# MCPS_Supply_030523.net
KiCad netlist of a schematic drawn in Altium Designer
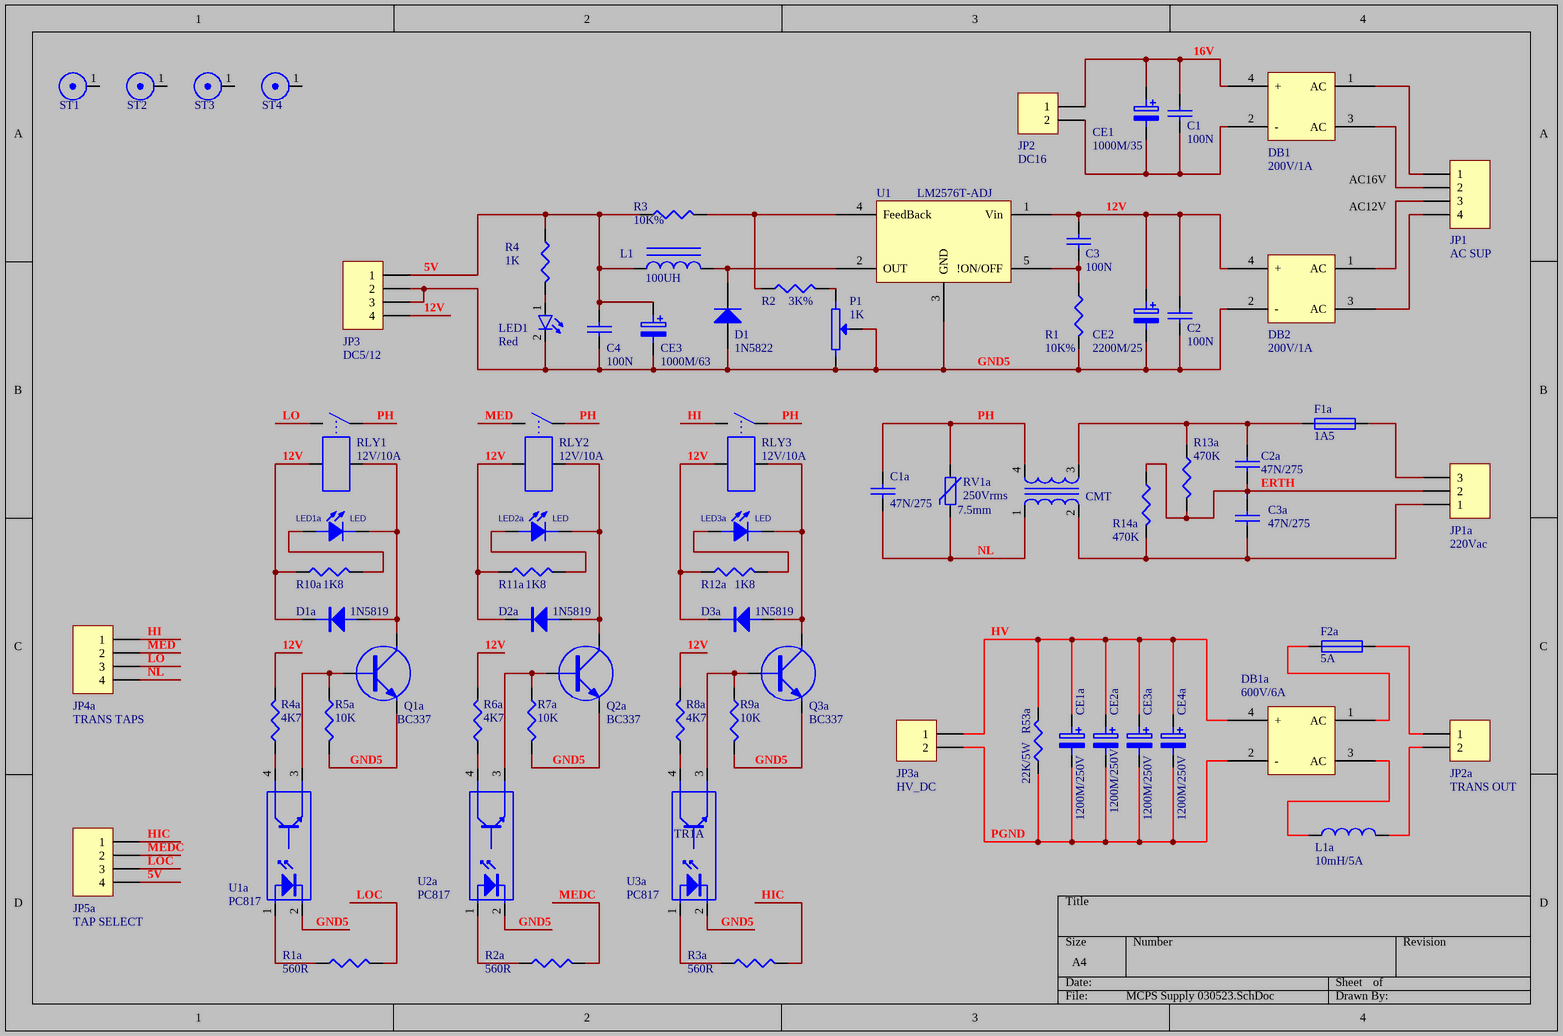
[diagram p0: MCPS Supply 030523.SchDoc]

(export (version "E")
  (design (tool "Eeschema 10.0.6"))
  (components
    (comp (ref "C1") (value "100N") (footprint "c1.8p") (libsource (lib "*") (part "C")))
    (comp (ref "C1a") (value "47N/275") (footprint "47N275") (libsource (lib "*") (part "C")))
    (comp (ref "C2") (value "100N") (footprint "c1.8p") (libsource (lib "*") (part "C")))
    (comp (ref "C2a") (value "47N/275") (footprint "47N275") (libsource (lib "*") (part "C")))
    (comp (ref "C3") (value "100N") (footprint "C3P") (libsource (lib "*") (part "C")))
    (comp (ref "C3a") (value "47N/275") (footprint "47N275") (libsource (lib "*") (part "C")))
    (comp (ref "C4") (value "100N") (footprint "c1.8p") (libsource (lib "*") (part "C")))
    (comp (ref "CE1") (value "1000M/35") (footprint "CAP3P") (libsource (lib "*") (part "E")))
    (comp (ref "CE1a") (value "1200M/250V") (footprint "CAP5P") (libsource (lib "*") (part "E")))
    (comp (ref "CE2") (value "2200M/25") (footprint "CAP3P") (libsource (lib "*") (part "E")))
    (comp (ref "CE2a") (value "1200M/250V") (footprint "CAP5P") (libsource (lib "*") (part "E")))
    (comp (ref "CE3") (value "1000M/63") (footprint "CAP2P") (libsource (lib "*") (part "E")))
    (comp (ref "CE3a") (value "1200M/250V") (footprint "CAP5P") (libsource (lib "*") (part "E")))
    (comp (ref "CE4a") (value "1200M/250V") (footprint "CAP5P") (libsource (lib "*") (part "E")))
    (comp (ref "D1")
      (value "1N5822")
      (footprint "d54")
      (description "Default Diode")
      (fields (field (name "PUBLISHER") "Altium Limited"))
      (libsource (lib "Miscellaneous Devices") (part "Diode"))
    )
    (comp (ref "D1a") (value "1N5819") (footprint "D54") (libsource (lib "MyAltiumLib9702") (part "D")))
    (comp (ref "D2a") (value "1N5819") (footprint "D54") (libsource (lib "MyAltiumLib9702") (part "D")))
    (comp (ref "D3a") (value "1N5819") (footprint "D54") (libsource (lib "MyAltiumLib9702") (part "D")))
    (comp (ref "DB1")
      (value "200V/1A")
      (footprint "BRG GBU")
      (libsource (lib "1402 Schlib 2020") (part "BRIDGE"))
    )
    (comp (ref "DB1a")
      (value "600V/6A")
      (footprint "BRIDGE S")
      (libsource (lib "1403 Schlib 2020") (part "BRIDGE"))
    )
    (comp (ref "DB2")
      (value "200V/1A")
      (footprint "BRG GBU")
      (libsource (lib "1402 Schlib 2020") (part "BRIDGE"))
    )
    (comp (ref "F1a") (value "1A5") (footprint "FS") (libsource (lib "1402 Schlib 2020") (part "FUSE1")))
    (comp (ref "F2a") (value "5A") (footprint "FS") (libsource (lib "1402 Schlib 2020") (part "FUSE1")))
    (comp (ref "JP1")
      (value "AC SUP")
      (description "Header, 4-Pin")
      (fields (field (name "PUBLISHER") "Altium Limited"))
      (libsource (lib "") (part "Header 4_1"))
    )
    (comp (ref "JP1a")
      (value "220Vac")
      (footprint "3EDG-str")
      (description "Header, 3-Pin")
      (fields (field (name "PUBLISHER") "Altium Limited"))
      (libsource (lib "1402 Schlib 2020") (part "Header 3"))
    )
    (comp (ref "JP2")
      (value "DC16")
      (footprint "2edg-str")
      (description "Header, 2-Pin")
      (fields (field (name "PUBLISHER") "Altium Limited"))
      (libsource (lib "Miscellaneous Connectors") (part "Header 2"))
    )
    (comp (ref "JP2a")
      (value "TRANS OUT")
      (footprint "2edg-str")
      (description "Header, 2-Pin")
      (fields (field (name "PUBLISHER") "Altium Limited"))
      (libsource (lib "") (part "Header 2_1"))
    )
    (comp (ref "JP3")
      (value "DC5/12")
      (description "Header, 4-Pin")
      (fields (field (name "PUBLISHER") "Altium Limited"))
      (libsource (lib "1403 Schlib 2020") (part "Header 4"))
    )
    (comp (ref "JP3a")
      (value "HV_DC")
      (footprint "DG55X2")
      (description "Header, 2-Pin")
      (fields (field (name "PUBLISHER") "Altium Limited"))
      (libsource (lib "Miscellaneous Connectors") (part "Header 2"))
    )
    (comp (ref "JP4a")
      (value "TRANS TAPS")
      (description "Header, 4-Pin")
      (fields (field (name "PUBLISHER") "Altium Limited"))
      (libsource (lib "1403 Schlib 2020") (part "Header 4"))
    )
    (comp (ref "JP5a")
      (value "TAP SELECT")
      (description "Header, 4-Pin")
      (fields (field (name "PUBLISHER") "Altium Limited"))
      (libsource (lib "1403 Schlib 2020") (part "Header 4"))
    )
    (comp (ref "L1") (value "100UH") (footprint "Inductor2512") (libsource (lib "*") (part "INDUCTOR IRON")))
    (comp (ref "L1a")
      (value "10mH/5A")
      (footprint "INDUCTOR2208")
      (libsource (lib "MyAltiumLib9702") (part "INDUCTOR"))
    )
    (comp (ref "LED1")
      (value "Red")
      (footprint "LED-5mm")
      (description "LED")
      (fields (field (name "COLOR") "Red") (field (name "DESIGNER") "Saeid Jorablo"))
      (libsource (lib "My Library") (part "LED"))
    )
    (comp (ref "LED1a")
      (value "LED")
      (footprint "LED-5mm")
      (description "LED LIGHTING")
      (fields (field (name "DESIGNER") "Abbas Basereh"))
      (libsource (lib "1403 Schlib 2020") (part "LED"))
    )
    (comp (ref "LED2a")
      (value "LED")
      (footprint "LED-5mm")
      (description "LED LIGHTING")
      (fields (field (name "DESIGNER") "Abbas Basereh"))
      (libsource (lib "1403 Schlib 2020") (part "LED"))
    )
    (comp (ref "LED3a")
      (value "LED")
      (footprint "LED-5mm")
      (description "LED LIGHTING")
      (fields (field (name "DESIGNER") "Abbas Basereh"))
      (libsource (lib "1403 Schlib 2020") (part "LED"))
    )
    (comp (ref "P1")
      (value "1K")
      (footprint "pot multi turn")
      (libsource (lib "1402 Schlib 2020") (part "POT2"))
    )
    (comp (ref "Q1a") (value "BC337") (footprint "139") (libsource (lib "1403 Schlib 2020") (part "N")))
    (comp (ref "Q2a") (value "BC337") (footprint "139") (libsource (lib "1403 Schlib 2020") (part "N")))
    (comp (ref "Q3a") (value "BC337") (footprint "139") (libsource (lib "1403 Schlib 2020") (part "N")))
    (comp (ref "R1") (value "10K%") (footprint "R4P") (libsource (lib "*") (part "R")))
    (comp (ref "R1a") (value "560R") (footprint "R4P") (libsource (lib "*") (part "R")))
    (comp (ref "R2") (value "3K%") (footprint "R4P") (libsource (lib "*") (part "R")))
    (comp (ref "R2a") (value "560R") (footprint "R4P") (libsource (lib "*") (part "R")))
    (comp (ref "R3") (value "10K%") (footprint "R4P") (libsource (lib "*") (part "R")))
    (comp (ref "R3a") (value "560R") (footprint "R4P") (libsource (lib "*") (part "R")))
    (comp (ref "R4") (value "1K") (footprint "R4P") (libsource (lib "*") (part "R")))
    (comp (ref "R4a") (value "4K7") (footprint "R4P") (libsource (lib "*") (part "R")))
    (comp (ref "R5a") (value "10K") (footprint "R4P") (libsource (lib "*") (part "R")))
    (comp (ref "R6a") (value "4K7") (footprint "R4P") (libsource (lib "*") (part "R")))
    (comp (ref "R7a") (value "10K") (footprint "R4P") (libsource (lib "*") (part "R")))
    (comp (ref "R8a") (value "4K7") (footprint "R4P") (libsource (lib "*") (part "R")))
    (comp (ref "R9a") (value "10K") (footprint "R4P") (libsource (lib "*") (part "R")))
    (comp (ref "R10a") (value "1K8") (footprint "R4P") (libsource (lib "*") (part "R")))
    (comp (ref "R11a") (value "1K8") (footprint "R4P") (libsource (lib "*") (part "R")))
    (comp (ref "R12a") (value "1K8") (footprint "R4P") (libsource (lib "*") (part "R")))
    (comp (ref "R13a") (value "470K") (footprint "R5P") (libsource (lib "*") (part "R")))
    (comp (ref "R14a") (value "470K") (footprint "R5P") (libsource (lib "*") (part "R")))
    (comp (ref "R53a") (value "22K/5W") (footprint "R4P") (libsource (lib "*") (part "R")))
    (comp (ref "RLY1") (value "12V/10A") (libsource (lib "1403 Schlib 2020") (part "RELAY-SPST4")))
    (comp (ref "RLY2") (value "12V/10A") (libsource (lib "1403 Schlib 2020") (part "RELAY-SPST4")))
    (comp (ref "RLY3") (value "12V/10A") (libsource (lib "1403 Schlib 2020") (part "RELAY-SPST4")))
    (comp (ref "RV1a")
      (value "250Vrms")
      (footprint "VARISTOR3")
      (libsource (lib "1402 Schlib 2020") (part "VARISTOR"))
    )
    (comp (ref "ST1") (value "STUD") (footprint "CORNER") (libsource (lib "1402 Schlib 2020") (part "STUD")))
    (comp (ref "ST2") (value "STUD") (footprint "CORNER") (libsource (lib "1402 Schlib 2020") (part "STUD")))
    (comp (ref "ST3") (value "STUD") (footprint "CORNER") (libsource (lib "1402 Schlib 2020") (part "STUD")))
    (comp (ref "ST4") (value "STUD") (footprint "CORNER") (libsource (lib "1402 Schlib 2020") (part "STUD")))
    (comp (ref "TR1A") (value "CMT") (footprint "CMT1") (libsource (lib "1402 Schlib 2020") (part "TRANS1")))
    (comp (ref "U1") (value "LM2576T-ADJ") (footprint "PENTA1") (libsource (lib "*") (part "LM2576")))
    (comp (ref "U1a")
      (value "PC817")
      (footprint "DIP4")
      (libsource (lib "1403 Schlib 2020") (part "OPTODIP4"))
    )
    (comp (ref "U2a")
      (value "PC817")
      (footprint "DIP4")
      (libsource (lib "1403 Schlib 2020") (part "OPTODIP4"))
    )
    (comp (ref "U3a")
      (value "PC817")
      (footprint "DIP4")
      (libsource (lib "1403 Schlib 2020") (part "OPTODIP4"))
    )
  )
  (nets
    (net (code "1") (name "/5V") (class "Default")
      (node (ref "C4") (pin "1") (pintype "passive"))
      (node (ref "CE3") (pin "1") (pintype "passive"))
      (node (ref "JP3") (pin "1") (pinfunction "1_1") (pintype "passive"))
      (node (ref "JP5a") (pin "4") (pinfunction "4_4") (pintype "passive"))
      (node (ref "L1") (pin "1") (pinfunction "1_1") (pintype "passive"))
      (node (ref "R3") (pin "1") (pintype "passive"))
      (node (ref "R4") (pin "1") (pintype "passive"))
    )
    (net (code "2") (name "/12V") (class "Default")
      (node (ref "C2") (pin "1") (pintype "passive"))
      (node (ref "C3") (pin "1") (pintype "passive"))
      (node (ref "CE2") (pin "1") (pintype "passive"))
      (node (ref "D1a") (pin "2") (pinfunction "K_2") (pintype "passive"))
      (node (ref "D2a") (pin "2") (pinfunction "K_2") (pintype "passive"))
      (node (ref "D3a") (pin "2") (pinfunction "K_2") (pintype "passive"))
      (node (ref "DB2") (pin "4") (pinfunction "+_4") (pintype "passive"))
      (node (ref "JP3") (pin "4") (pinfunction "4_4") (pintype "passive"))
      (node (ref "R10a") (pin "1") (pintype "passive"))
      (node (ref "R11a") (pin "1") (pintype "passive"))
      (node (ref "R12a") (pin "1") (pintype "passive"))
      (node (ref "R4a") (pin "2") (pintype "passive"))
      (node (ref "R6a") (pin "2") (pintype "passive"))
      (node (ref "R8a") (pin "2") (pintype "passive"))
      (node (ref "RLY1") (pin "5") (pintype "passive"))
      (node (ref "RLY2") (pin "5") (pintype "passive"))
      (node (ref "RLY3") (pin "5") (pintype "passive"))
      (node (ref "U1") (pin "1") (pinfunction "Vin_1") (pintype "passive"))
    )
    (net (code "3") (name "/16V") (class "Default")
      (node (ref "C1") (pin "1") (pintype "passive"))
      (node (ref "CE1") (pin "1") (pintype "passive"))
      (node (ref "DB1") (pin "4") (pinfunction "+_4") (pintype "passive"))
      (node (ref "JP2") (pin "1") (pinfunction "1_1") (pintype "passive"))
    )
    (net (code "4") (name "/ERTH") (class "Default")
      (node (ref "C2a") (pin "2") (pintype "passive"))
      (node (ref "C3a") (pin "1") (pintype "passive"))
      (node (ref "JP1a") (pin "2") (pinfunction "2_2") (pintype "passive"))
      (node (ref "R13a") (pin "2") (pintype "passive"))
      (node (ref "R14a") (pin "1") (pintype "passive"))
    )
    (net (code "5") (name "/GND5") (class "Default")
      (node (ref "C2") (pin "2") (pintype "passive"))
      (node (ref "C4") (pin "2") (pintype "passive"))
      (node (ref "CE2") (pin "2") (pintype "passive"))
      (node (ref "CE3") (pin "2") (pintype "passive"))
      (node (ref "D1") (pin "1") (pinfunction "A_1") (pintype "passive"))
      (node (ref "DB2") (pin "2") (pinfunction "-_2") (pintype "passive"))
      (node (ref "JP3") (pin "2") (pinfunction "2_2") (pintype "passive"))
      (node (ref "JP3") (pin "3") (pinfunction "3_3") (pintype "passive"))
      (node (ref "LED1") (pin "2") (pinfunction "K_2") (pintype "passive"))
      (node (ref "P1") (pin "2") (pintype "passive"))
      (node (ref "P1") (pin "3") (pintype "passive"))
      (node (ref "Q1a") (pin "1") (pinfunction "E_1") (pintype "passive"))
      (node (ref "Q2a") (pin "1") (pinfunction "E_1") (pintype "passive"))
      (node (ref "Q3a") (pin "1") (pinfunction "E_1") (pintype "passive"))
      (node (ref "R1") (pin "2") (pintype "passive"))
      (node (ref "R5a") (pin "2") (pintype "passive"))
      (node (ref "R7a") (pin "2") (pintype "passive"))
      (node (ref "R9a") (pin "2") (pintype "passive"))
      (node (ref "U1") (pin "3") (pinfunction "GND_3") (pintype "passive"))
      (node (ref "U1a") (pin "2") (pinfunction "K_2") (pintype "passive"))
      (node (ref "U2a") (pin "2") (pinfunction "K_2") (pintype "passive"))
      (node (ref "U3a") (pin "2") (pinfunction "K_2") (pintype "passive"))
    )
    (net (code "6") (name "/HI") (class "Default")
      (node (ref "JP4a") (pin "1") (pinfunction "1_1") (pintype "passive"))
      (node (ref "RLY3") (pin "2") (pintype "passive"))
    )
    (net (code "7") (name "/HIC") (class "Default")
      (node (ref "JP5a") (pin "1") (pinfunction "1_1") (pintype "passive"))
      (node (ref "R3a") (pin "2") (pintype "passive"))
    )
    (net (code "8") (name "/HV") (class "Default")
      (node (ref "CE1a") (pin "1") (pintype "passive"))
      (node (ref "CE2a") (pin "1") (pintype "passive"))
      (node (ref "CE3a") (pin "1") (pintype "passive"))
      (node (ref "CE4a") (pin "1") (pintype "passive"))
      (node (ref "DB1a") (pin "4") (pinfunction "+_4") (pintype "passive"))
      (node (ref "JP3a") (pin "1") (pinfunction "1_1") (pintype "passive"))
      (node (ref "R53a") (pin "2") (pintype "passive"))
    )
    (net (code "9") (name "/LO") (class "Default")
      (node (ref "JP4a") (pin "3") (pinfunction "3_3") (pintype "passive"))
      (node (ref "RLY1") (pin "2") (pintype "passive"))
    )
    (net (code "10") (name "/LOC") (class "Default")
      (node (ref "JP5a") (pin "3") (pinfunction "3_3") (pintype "passive"))
      (node (ref "R1a") (pin "2") (pintype "passive"))
    )
    (net (code "11") (name "/MED") (class "Default")
      (node (ref "JP4a") (pin "2") (pinfunction "2_2") (pintype "passive"))
      (node (ref "RLY2") (pin "2") (pintype "passive"))
    )
    (net (code "12") (name "/MEDC") (class "Default")
      (node (ref "JP5a") (pin "2") (pinfunction "2_2") (pintype "passive"))
      (node (ref "R2a") (pin "2") (pintype "passive"))
    )
    (net (code "13") (name "/NL") (class "Default")
      (node (ref "C1a") (pin "2") (pintype "passive"))
      (node (ref "JP4a") (pin "4") (pinfunction "4_4") (pintype "passive"))
      (node (ref "RV1a") (pin "2") (pinfunction "2_2") (pintype "passive"))
      (node (ref "TR1A") (pin "1") (pintype "passive"))
    )
    (net (code "14") (name "/PGND") (class "Default")
      (node (ref "CE1a") (pin "2") (pintype "passive"))
      (node (ref "CE2a") (pin "2") (pintype "passive"))
      (node (ref "CE3a") (pin "2") (pintype "passive"))
      (node (ref "CE4a") (pin "2") (pintype "passive"))
      (node (ref "DB1a") (pin "2") (pinfunction "-_2") (pintype "passive"))
      (node (ref "JP3a") (pin "2") (pinfunction "2_2") (pintype "passive"))
      (node (ref "R53a") (pin "1") (pintype "passive"))
    )
    (net (code "15") (name "/PH") (class "Default")
      (node (ref "C1a") (pin "1") (pintype "passive"))
      (node (ref "RLY1") (pin "1") (pintype "passive"))
      (node (ref "RLY2") (pin "1") (pintype "passive"))
      (node (ref "RLY3") (pin "1") (pintype "passive"))
      (node (ref "RV1a") (pin "1") (pinfunction "1_1") (pintype "passive"))
      (node (ref "TR1A") (pin "4") (pintype "passive"))
    )
    (net (code "16") (name "Net-(C2a-Pad1)") (class "Default")
      (node (ref "C2a") (pin "1") (pintype "passive"))
      (node (ref "F1a") (pin "2") (pintype "passive"))
      (node (ref "R13a") (pin "1") (pintype "passive"))
      (node (ref "TR1A") (pin "3") (pintype "passive"))
    )
    (net (code "17") (name "Net-(C3a-Pad2)") (class "Default")
      (node (ref "C3a") (pin "2") (pintype "passive"))
      (node (ref "JP1a") (pin "1") (pinfunction "1_1") (pintype "passive"))
      (node (ref "R14a") (pin "2") (pintype "passive"))
      (node (ref "TR1A") (pin "2") (pintype "passive"))
    )
    (net (code "18") (name "Net-(D1-K)") (class "Default")
      (node (ref "D1") (pin "2") (pinfunction "K_2") (pintype "passive"))
      (node (ref "L1") (pin "2") (pinfunction "2_2") (pintype "passive"))
      (node (ref "U1") (pin "2") (pinfunction "OUT_2") (pintype "passive"))
    )
    (net (code "19") (name "Net-(D1a-A)") (class "Default")
      (node (ref "D1a") (pin "1") (pinfunction "A_1") (pintype "passive"))
      (node (ref "LED1a") (pin "2") (pinfunction "CATHODE_2") (pintype "passive"))
      (node (ref "Q1a") (pin "3") (pinfunction "C_3") (pintype "passive"))
      (node (ref "RLY1") (pin "4") (pintype "passive"))
    )
    (net (code "20") (name "Net-(D2a-A)") (class "Default")
      (node (ref "D2a") (pin "1") (pinfunction "A_1") (pintype "passive"))
      (node (ref "LED2a") (pin "2") (pinfunction "CATHODE_2") (pintype "passive"))
      (node (ref "Q2a") (pin "3") (pinfunction "C_3") (pintype "passive"))
      (node (ref "RLY2") (pin "4") (pintype "passive"))
    )
    (net (code "21") (name "Net-(D3a-A)") (class "Default")
      (node (ref "D3a") (pin "1") (pinfunction "A_1") (pintype "passive"))
      (node (ref "LED3a") (pin "2") (pinfunction "CATHODE_2") (pintype "passive"))
      (node (ref "Q3a") (pin "3") (pinfunction "C_3") (pintype "passive"))
      (node (ref "RLY3") (pin "4") (pintype "passive"))
    )
    (net (code "22") (name "Net-(DB1--)") (class "Default")
      (node (ref "C1") (pin "2") (pintype "passive"))
      (node (ref "CE1") (pin "2") (pintype "passive"))
      (node (ref "DB1") (pin "2") (pinfunction "-_2") (pintype "passive"))
      (node (ref "JP2") (pin "2") (pinfunction "2_2") (pintype "passive"))
    )
    (net (code "23") (name "Net-(DB1-AC-Pad1)") (class "Default")
      (node (ref "DB1") (pin "1") (pinfunction "AC_1") (pintype "passive"))
      (node (ref "JP1") (pin "1") (pinfunction "1_1") (pintype "passive"))
    )
    (net (code "24") (name "Net-(DB1-AC-Pad3)") (class "Default")
      (node (ref "DB1") (pin "3") (pinfunction "AC_3") (pintype "passive"))
      (node (ref "JP1") (pin "2") (pinfunction "2_2") (pintype "passive"))
    )
    (net (code "25") (name "Net-(DB1a-AC-Pad1)") (class "Default")
      (node (ref "DB1a") (pin "1") (pinfunction "AC_1") (pintype "passive"))
      (node (ref "F2a") (pin "1") (pintype "passive"))
    )
    (net (code "26") (name "Net-(DB1a-AC-Pad3)") (class "Default")
      (node (ref "DB1a") (pin "3") (pinfunction "AC_3") (pintype "passive"))
      (node (ref "L1a") (pin "1") (pinfunction "1_1") (pintype "passive"))
    )
    (net (code "27") (name "Net-(DB2-AC-Pad1)") (class "Default")
      (node (ref "DB2") (pin "1") (pinfunction "AC_1") (pintype "passive"))
      (node (ref "JP1") (pin "3") (pinfunction "3_3") (pintype "passive"))
    )
    (net (code "28") (name "Net-(DB2-AC-Pad3)") (class "Default")
      (node (ref "DB2") (pin "3") (pinfunction "AC_3") (pintype "passive"))
      (node (ref "JP1") (pin "4") (pinfunction "4_4") (pintype "passive"))
    )
    (net (code "29") (name "Net-(F1a-Pad1)") (class "Default")
      (node (ref "F1a") (pin "1") (pintype "passive"))
      (node (ref "JP1a") (pin "3") (pinfunction "3_3") (pintype "passive"))
    )
    (net (code "30") (name "Net-(F2a-Pad2)") (class "Default")
      (node (ref "F2a") (pin "2") (pintype "passive"))
      (node (ref "JP2a") (pin "1") (pinfunction "1_1") (pintype "passive"))
    )
    (net (code "31") (name "Net-(JP2a-Pad2)") (class "Default")
      (node (ref "JP2a") (pin "2") (pinfunction "2_2") (pintype "passive"))
      (node (ref "L1a") (pin "2") (pinfunction "2_2") (pintype "passive"))
    )
    (net (code "32") (name "Net-(LED1-A)") (class "Default")
      (node (ref "LED1") (pin "1") (pinfunction "A_1") (pintype "passive"))
      (node (ref "R4") (pin "2") (pintype "passive"))
    )
    (net (code "33") (name "Net-(LED1a-ANODE)") (class "Default")
      (node (ref "LED1a") (pin "1") (pinfunction "ANODE_1") (pintype "passive"))
      (node (ref "R10a") (pin "2") (pintype "passive"))
    )
    (net (code "34") (name "Net-(LED2a-ANODE)") (class "Default")
      (node (ref "LED2a") (pin "1") (pinfunction "ANODE_1") (pintype "passive"))
      (node (ref "R11a") (pin "2") (pintype "passive"))
    )
    (net (code "35") (name "Net-(LED3a-ANODE)") (class "Default")
      (node (ref "LED3a") (pin "1") (pinfunction "ANODE_1") (pintype "passive"))
      (node (ref "R12a") (pin "2") (pintype "passive"))
    )
    (net (code "36") (name "Net-(P1-Pad1)") (class "Default")
      (node (ref "P1") (pin "1") (pintype "passive"))
      (node (ref "R2") (pin "2") (pintype "passive"))
    )
    (net (code "37") (name "Net-(Q1a-B)") (class "Default")
      (node (ref "Q1a") (pin "2") (pinfunction "B_2") (pintype "passive"))
      (node (ref "R5a") (pin "1") (pintype "passive"))
      (node (ref "U1a") (pin "3") (pinfunction "E_3") (pintype "passive"))
    )
    (net (code "38") (name "Net-(Q2a-B)") (class "Default")
      (node (ref "Q2a") (pin "2") (pinfunction "B_2") (pintype "passive"))
      (node (ref "R7a") (pin "1") (pintype "passive"))
      (node (ref "U2a") (pin "3") (pinfunction "E_3") (pintype "passive"))
    )
    (net (code "39") (name "Net-(Q3a-B)") (class "Default")
      (node (ref "Q3a") (pin "2") (pinfunction "B_2") (pintype "passive"))
      (node (ref "R9a") (pin "1") (pintype "passive"))
      (node (ref "U3a") (pin "3") (pinfunction "E_3") (pintype "passive"))
    )
    (net (code "40") (name "Net-(U1-!ON{slash}OFF)") (class "Default")
      (node (ref "C3") (pin "2") (pintype "passive"))
      (node (ref "R1") (pin "1") (pintype "passive"))
      (node (ref "U1") (pin "5") (pinfunction "!ON/OFF_5") (pintype "passive"))
    )
    (net (code "41") (name "Net-(U1-FeedBack)") (class "Default")
      (node (ref "R2") (pin "1") (pintype "passive"))
      (node (ref "R3") (pin "2") (pintype "passive"))
      (node (ref "U1") (pin "4") (pinfunction "FeedBack_4") (pintype "passive"))
    )
    (net (code "42") (name "Net-(U1a-A)") (class "Default")
      (node (ref "R1a") (pin "1") (pintype "passive"))
      (node (ref "U1a") (pin "1") (pinfunction "A_1") (pintype "passive"))
    )
    (net (code "43") (name "Net-(U1a-C)") (class "Default")
      (node (ref "R4a") (pin "1") (pintype "passive"))
      (node (ref "U1a") (pin "4") (pinfunction "C_4") (pintype "passive"))
    )
    (net (code "44") (name "Net-(U2a-A)") (class "Default")
      (node (ref "R2a") (pin "1") (pintype "passive"))
      (node (ref "U2a") (pin "1") (pinfunction "A_1") (pintype "passive"))
    )
    (net (code "45") (name "Net-(U2a-C)") (class "Default")
      (node (ref "R6a") (pin "1") (pintype "passive"))
      (node (ref "U2a") (pin "4") (pinfunction "C_4") (pintype "passive"))
    )
    (net (code "46") (name "Net-(U3a-A)") (class "Default")
      (node (ref "R3a") (pin "1") (pintype "passive"))
      (node (ref "U3a") (pin "1") (pinfunction "A_1") (pintype "passive"))
    )
    (net (code "47") (name "Net-(U3a-C)") (class "Default")
      (node (ref "R8a") (pin "1") (pintype "passive"))
      (node (ref "U3a") (pin "4") (pinfunction "C_4") (pintype "passive"))
    )
    (net (code "48") (name "unconnected-(ST1-Pad1)") (class "Default")
      (node (ref "ST1") (pin "1") (pintype "passive"))
    )
    (net (code "49") (name "unconnected-(ST2-Pad1)") (class "Default")
      (node (ref "ST2") (pin "1") (pintype "passive"))
    )
    (net (code "50") (name "unconnected-(ST3-Pad1)") (class "Default")
      (node (ref "ST3") (pin "1") (pintype "passive"))
    )
    (net (code "51") (name "unconnected-(ST4-Pad1)") (class "Default")
      (node (ref "ST4") (pin "1") (pintype "passive"))
    )
  )
)
